# zesilovac.net
KiCad netlist of a schematic drawn in EAGLE
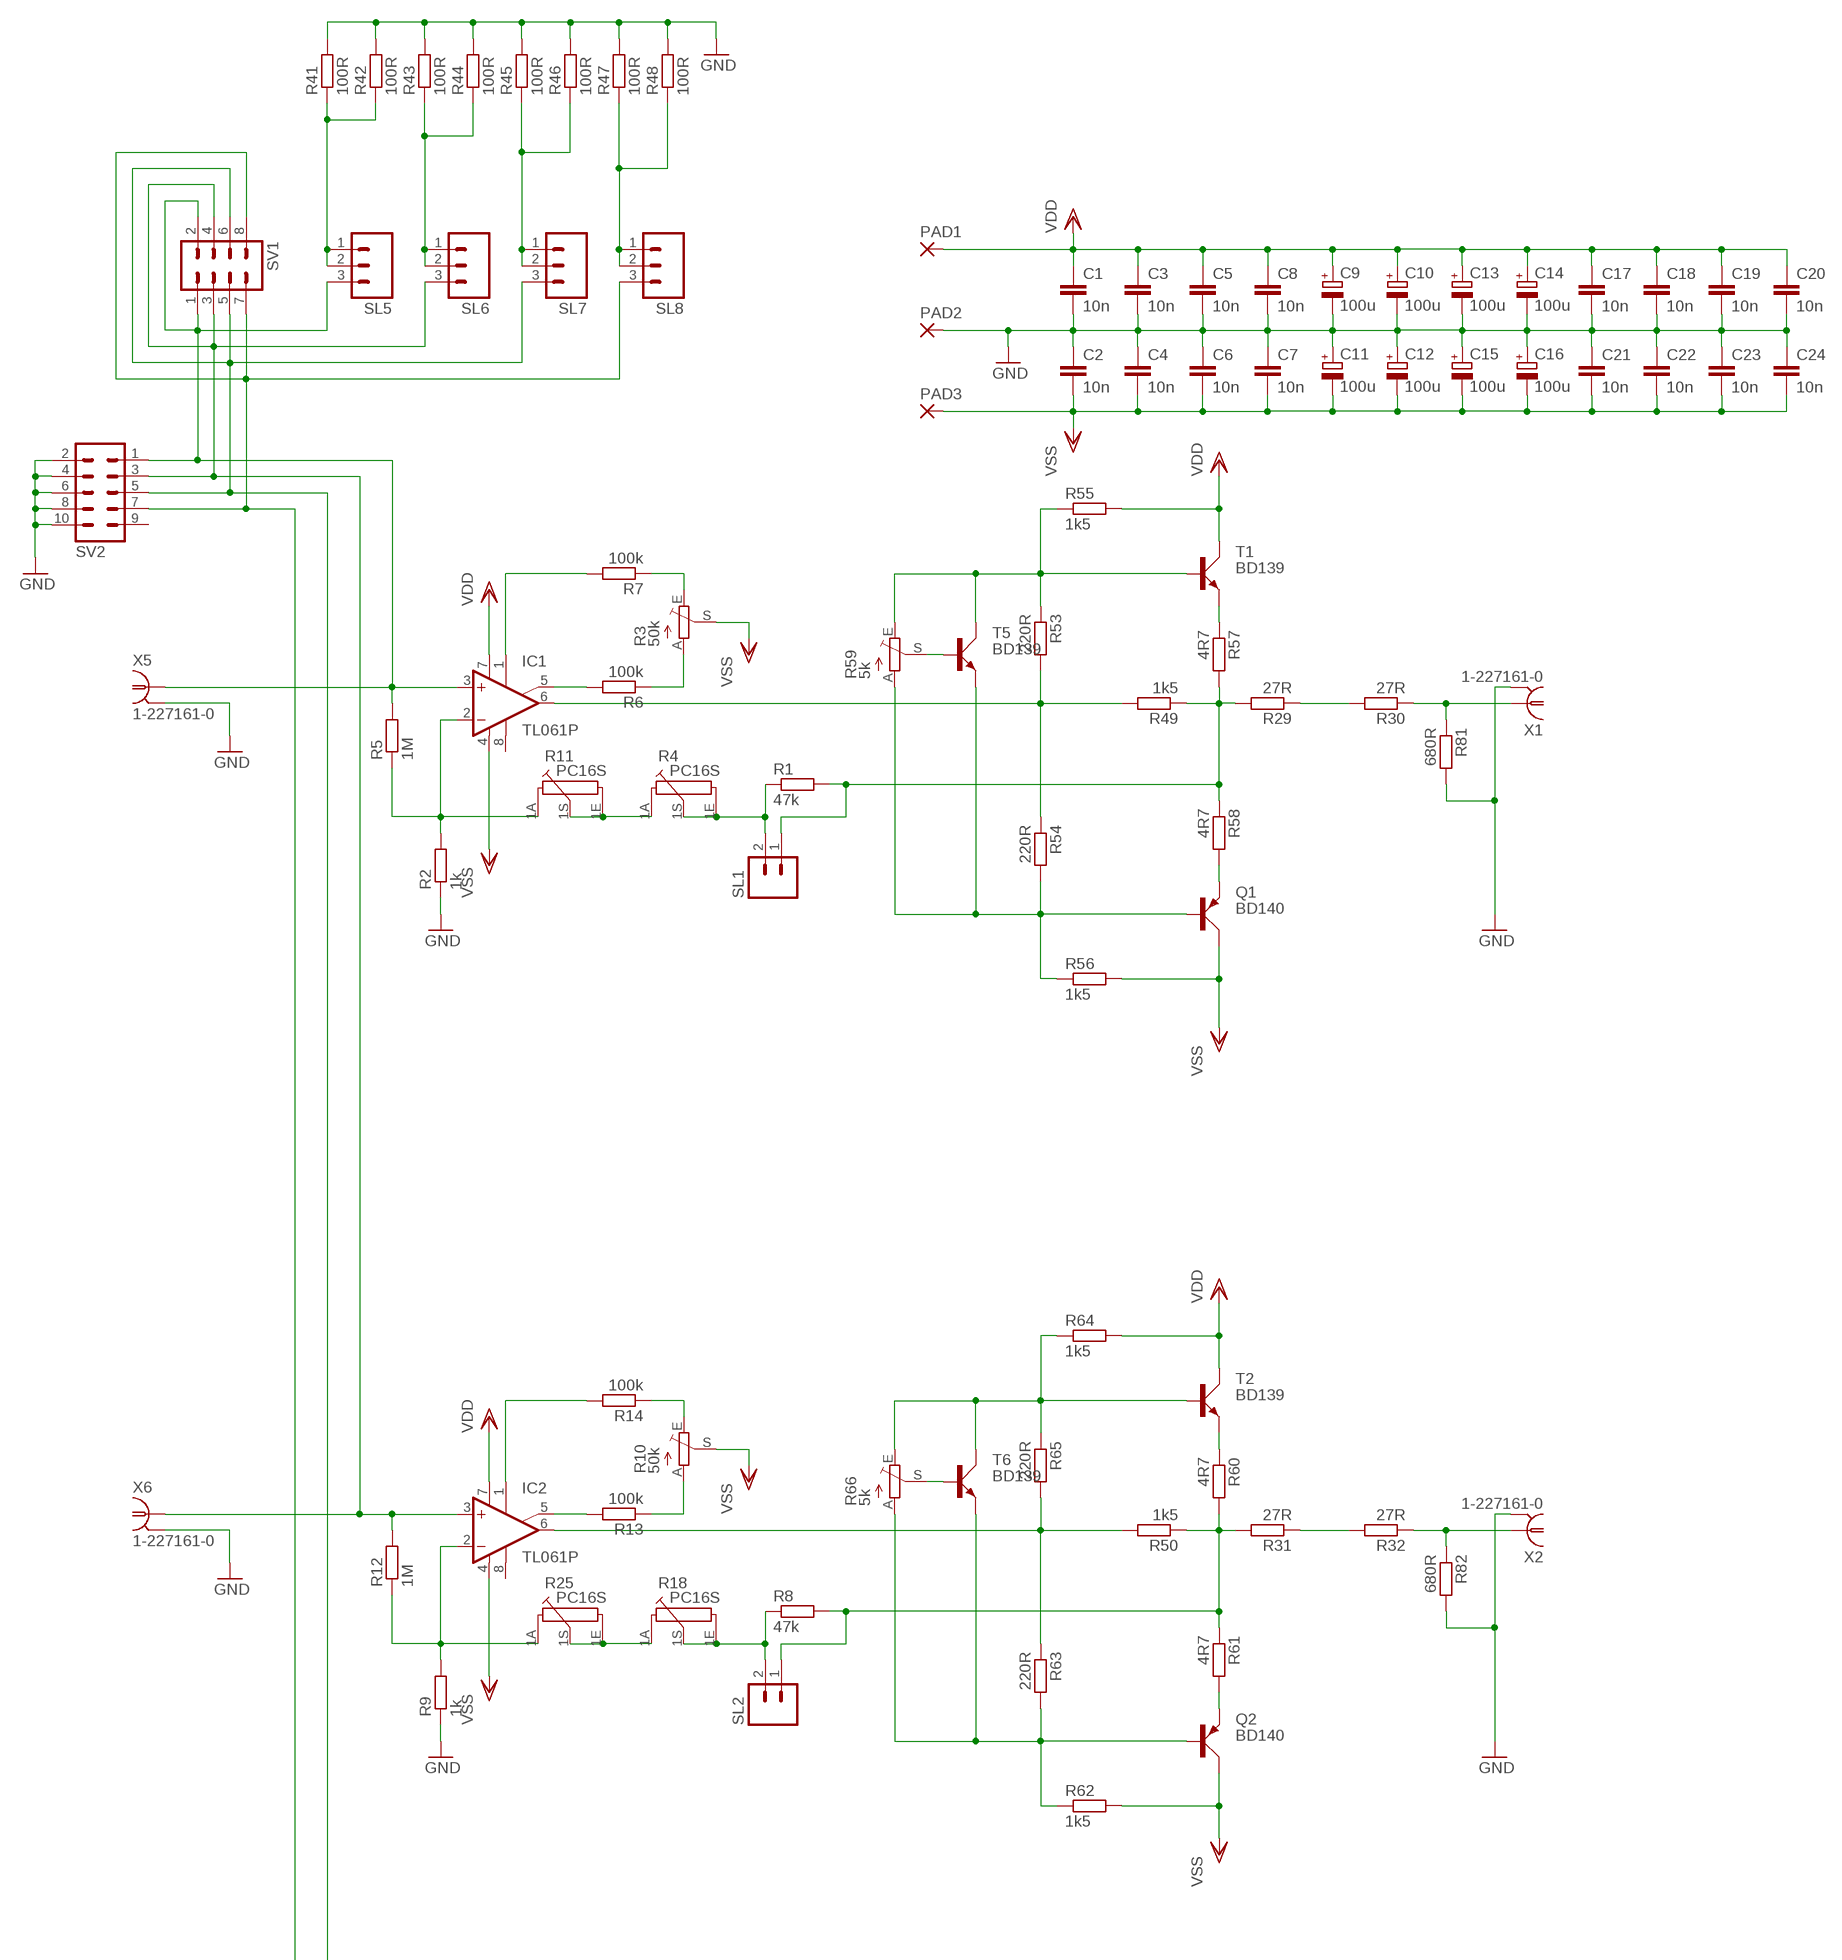
[diagram p0: schematic, sheet 1, part 1 of 2]
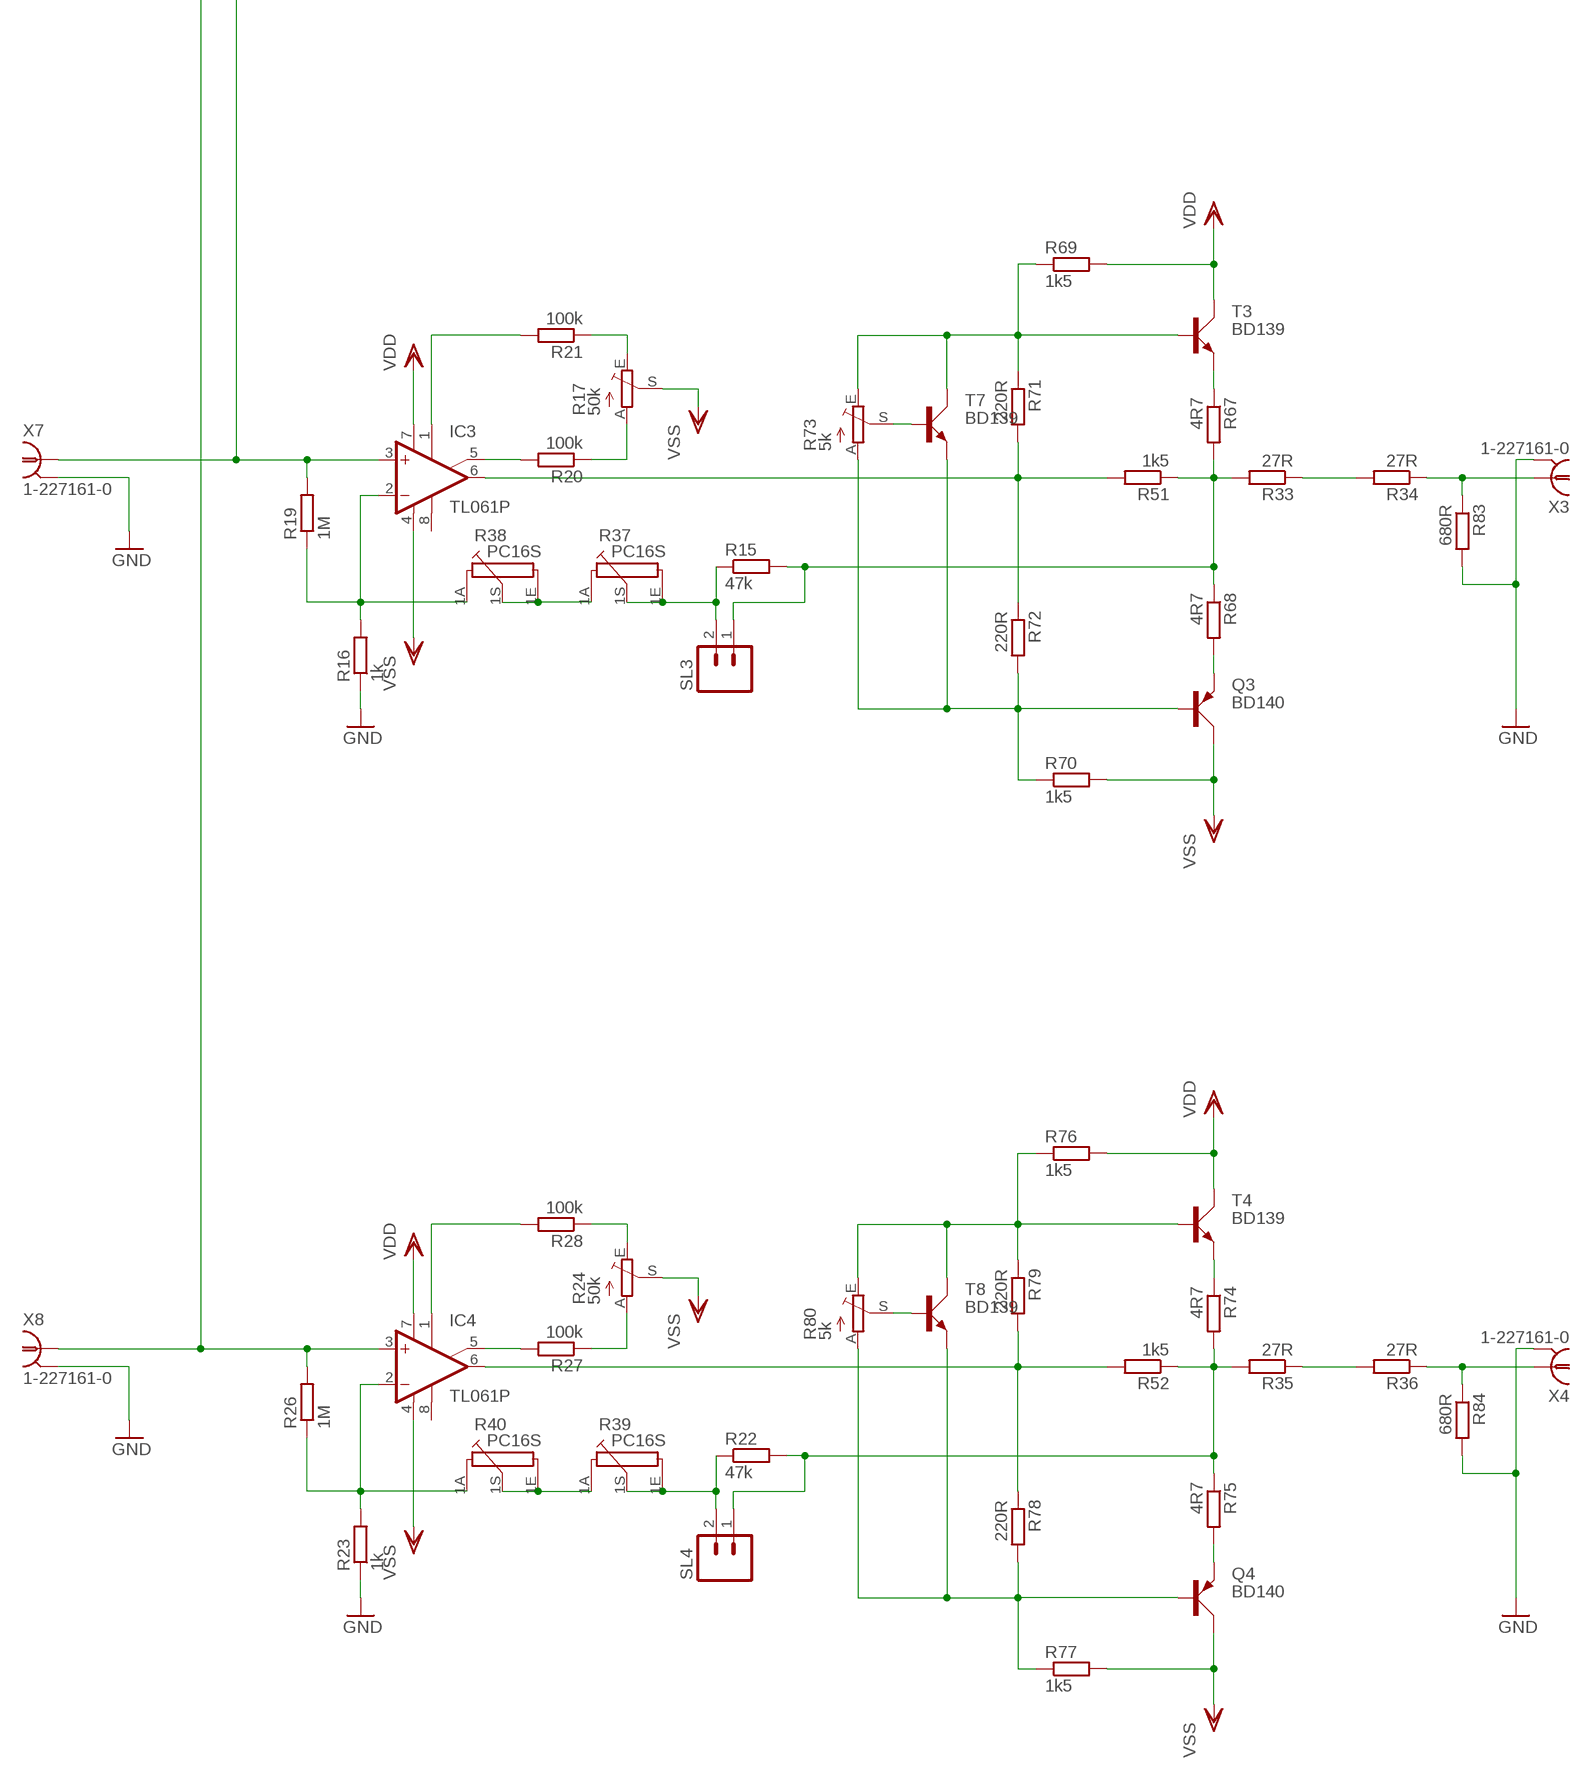
[diagram p1: schematic, sheet 1, part 2 of 2]

(export (version "E")
  (design (tool "Eeschema 10.0.6"))
  (components
    (comp (ref "C1")
      (value "10n")
      (footprint "eagle-import:C5B5")
      (libsource (lib "eagle-import") (part "C5/5"))
    )
    (comp (ref "C2")
      (value "10n")
      (footprint "eagle-import:C5B5")
      (libsource (lib "eagle-import") (part "C5/5"))
    )
    (comp (ref "C3")
      (value "10n")
      (footprint "eagle-import:C5B5")
      (libsource (lib "eagle-import") (part "C5/5"))
    )
    (comp (ref "C4")
      (value "10n")
      (footprint "eagle-import:C5B5")
      (libsource (lib "eagle-import") (part "C5/5"))
    )
    (comp (ref "C5")
      (value "10n")
      (footprint "eagle-import:C5B5")
      (libsource (lib "eagle-import") (part "C5/5"))
    )
    (comp (ref "C6")
      (value "10n")
      (footprint "eagle-import:C5B5")
      (libsource (lib "eagle-import") (part "C5/5"))
    )
    (comp (ref "C7")
      (value "10n")
      (footprint "eagle-import:C5B5")
      (libsource (lib "eagle-import") (part "C5/5"))
    )
    (comp (ref "C8")
      (value "10n")
      (footprint "eagle-import:C5B5")
      (libsource (lib "eagle-import") (part "C5/5"))
    )
    (comp (ref "C9")
      (value "100u")
      (footprint "eagle-import:E5-13")
      (libsource (lib "eagle-import") (part "CPOL-EUE5-13"))
    )
    (comp (ref "C10")
      (value "100u")
      (footprint "eagle-import:E5-13")
      (libsource (lib "eagle-import") (part "CPOL-EUE5-13"))
    )
    (comp (ref "C11")
      (value "100u")
      (footprint "eagle-import:E5-13")
      (libsource (lib "eagle-import") (part "CPOL-EUE5-13"))
    )
    (comp (ref "C12")
      (value "100u")
      (footprint "eagle-import:E5-13")
      (libsource (lib "eagle-import") (part "CPOL-EUE5-13"))
    )
    (comp (ref "C13")
      (value "100u")
      (footprint "eagle-import:E5-13")
      (libsource (lib "eagle-import") (part "CPOL-EUE5-13"))
    )
    (comp (ref "C14")
      (value "100u")
      (footprint "eagle-import:E5-13")
      (libsource (lib "eagle-import") (part "CPOL-EUE5-13"))
    )
    (comp (ref "C15")
      (value "100u")
      (footprint "eagle-import:E5-13")
      (libsource (lib "eagle-import") (part "CPOL-EUE5-13"))
    )
    (comp (ref "C16")
      (value "100u")
      (footprint "eagle-import:E5-13")
      (libsource (lib "eagle-import") (part "CPOL-EUE5-13"))
    )
    (comp (ref "C17")
      (value "10n")
      (footprint "eagle-import:C5B5")
      (libsource (lib "eagle-import") (part "C5/5"))
    )
    (comp (ref "C18")
      (value "10n")
      (footprint "eagle-import:C5B5")
      (libsource (lib "eagle-import") (part "C5/5"))
    )
    (comp (ref "C19")
      (value "10n")
      (footprint "eagle-import:C5B5")
      (libsource (lib "eagle-import") (part "C5/5"))
    )
    (comp (ref "C20")
      (value "10n")
      (footprint "eagle-import:C5B5")
      (libsource (lib "eagle-import") (part "C5/5"))
    )
    (comp (ref "C21")
      (value "10n")
      (footprint "eagle-import:C5B5")
      (libsource (lib "eagle-import") (part "C5/5"))
    )
    (comp (ref "C22")
      (value "10n")
      (footprint "eagle-import:C5B5")
      (libsource (lib "eagle-import") (part "C5/5"))
    )
    (comp (ref "C23")
      (value "10n")
      (footprint "eagle-import:C5B5")
      (libsource (lib "eagle-import") (part "C5/5"))
    )
    (comp (ref "C24")
      (value "10n")
      (footprint "eagle-import:C5B5")
      (libsource (lib "eagle-import") (part "C5/5"))
    )
    (comp (ref "IC1")
      (value "TL061P")
      (footprint "eagle-import:DIL08")
      (libsource (lib "eagle-import") (part "TL061P"))
    )
    (comp (ref "IC2")
      (value "TL061P")
      (footprint "eagle-import:DIL08")
      (libsource (lib "eagle-import") (part "TL061P"))
    )
    (comp (ref "IC3")
      (value "TL061P")
      (footprint "eagle-import:DIL08")
      (libsource (lib "eagle-import") (part "TL061P"))
    )
    (comp (ref "IC4")
      (value "TL061P")
      (footprint "eagle-import:DIL08")
      (libsource (lib "eagle-import") (part "TL061P"))
    )
    (comp (ref "PAD1")
      (value "3,81/1,4")
      (footprint "eagle-import:3,81_1,4")
      (libsource (lib "eagle-import") (part "3,81/1,4"))
    )
    (comp (ref "PAD2")
      (value "3,81/1,4")
      (footprint "eagle-import:3,81_1,4")
      (libsource (lib "eagle-import") (part "3,81/1,4"))
    )
    (comp (ref "PAD3")
      (value "3,81/1,4")
      (footprint "eagle-import:3,81_1,4")
      (libsource (lib "eagle-import") (part "3,81/1,4"))
    )
    (comp (ref "Q1")
      (value "BD140")
      (footprint "eagle-import:TO126AV")
      (libsource (lib "eagle-import") (part "BD140"))
    )
    (comp (ref "Q2")
      (value "BD140")
      (footprint "eagle-import:TO126AV")
      (libsource (lib "eagle-import") (part "BD140"))
    )
    (comp (ref "Q3")
      (value "BD140")
      (footprint "eagle-import:TO126AV")
      (libsource (lib "eagle-import") (part "BD140"))
    )
    (comp (ref "Q4")
      (value "BD140")
      (footprint "eagle-import:TO126AV")
      (libsource (lib "eagle-import") (part "BD140"))
    )
    (comp (ref "R1")
      (value "47k")
      (footprint "eagle-import:0207_12")
      (libsource (lib "eagle-import") (part "R-EU_0207/12"))
    )
    (comp (ref "R2")
      (value "1k")
      (footprint "eagle-import:0207_12")
      (libsource (lib "eagle-import") (part "R-EU_0207/12"))
    )
    (comp (ref "R3")
      (value "50k")
      (footprint "eagle-import:LI10")
      (libsource (lib "eagle-import") (part "TRIM_EU-LI10"))
    )
    (comp (ref "R4")
      (value "PC16S")
      (footprint "eagle-import:PC16S")
      (libsource (lib "eagle-import") (part "PC16S"))
    )
    (comp (ref "R5")
      (value "1M")
      (footprint "eagle-import:0207_12")
      (libsource (lib "eagle-import") (part "R-EU_0207/12"))
    )
    (comp (ref "R6")
      (value "100k")
      (footprint "eagle-import:0207_12")
      (libsource (lib "eagle-import") (part "R-EU_0207/12"))
    )
    (comp (ref "R7")
      (value "100k")
      (footprint "eagle-import:0207_12")
      (libsource (lib "eagle-import") (part "R-EU_0207/12"))
    )
    (comp (ref "R8")
      (value "47k")
      (footprint "eagle-import:0207_12")
      (libsource (lib "eagle-import") (part "R-EU_0207/12"))
    )
    (comp (ref "R9")
      (value "1k")
      (footprint "eagle-import:0207_12")
      (libsource (lib "eagle-import") (part "R-EU_0207/12"))
    )
    (comp (ref "R10")
      (value "50k")
      (footprint "eagle-import:LI10")
      (libsource (lib "eagle-import") (part "TRIM_EU-LI10"))
    )
    (comp (ref "R11")
      (value "PC16S")
      (footprint "eagle-import:PC16S")
      (libsource (lib "eagle-import") (part "PC16S"))
    )
    (comp (ref "R12")
      (value "1M")
      (footprint "eagle-import:0207_12")
      (libsource (lib "eagle-import") (part "R-EU_0207/12"))
    )
    (comp (ref "R13")
      (value "100k")
      (footprint "eagle-import:0207_12")
      (libsource (lib "eagle-import") (part "R-EU_0207/12"))
    )
    (comp (ref "R14")
      (value "100k")
      (footprint "eagle-import:0207_12")
      (libsource (lib "eagle-import") (part "R-EU_0207/12"))
    )
    (comp (ref "R15")
      (value "47k")
      (footprint "eagle-import:0207_12")
      (libsource (lib "eagle-import") (part "R-EU_0207/12"))
    )
    (comp (ref "R16")
      (value "1k")
      (footprint "eagle-import:0207_12")
      (libsource (lib "eagle-import") (part "R-EU_0207/12"))
    )
    (comp (ref "R17")
      (value "50k")
      (footprint "eagle-import:LI10")
      (libsource (lib "eagle-import") (part "TRIM_EU-LI10"))
    )
    (comp (ref "R18")
      (value "PC16S")
      (footprint "eagle-import:PC16S")
      (libsource (lib "eagle-import") (part "PC16S"))
    )
    (comp (ref "R19")
      (value "1M")
      (footprint "eagle-import:0207_12")
      (libsource (lib "eagle-import") (part "R-EU_0207/12"))
    )
    (comp (ref "R20")
      (value "100k")
      (footprint "eagle-import:0207_12")
      (libsource (lib "eagle-import") (part "R-EU_0207/12"))
    )
    (comp (ref "R21")
      (value "100k")
      (footprint "eagle-import:0207_12")
      (libsource (lib "eagle-import") (part "R-EU_0207/12"))
    )
    (comp (ref "R22")
      (value "47k")
      (footprint "eagle-import:0207_12")
      (libsource (lib "eagle-import") (part "R-EU_0207/12"))
    )
    (comp (ref "R23")
      (value "1k")
      (footprint "eagle-import:0207_12")
      (libsource (lib "eagle-import") (part "R-EU_0207/12"))
    )
    (comp (ref "R24")
      (value "50k")
      (footprint "eagle-import:LI10")
      (libsource (lib "eagle-import") (part "TRIM_EU-LI10"))
    )
    (comp (ref "R25")
      (value "PC16S")
      (footprint "eagle-import:PC16S")
      (libsource (lib "eagle-import") (part "PC16S"))
    )
    (comp (ref "R26")
      (value "1M")
      (footprint "eagle-import:0207_12")
      (libsource (lib "eagle-import") (part "R-EU_0207/12"))
    )
    (comp (ref "R27")
      (value "100k")
      (footprint "eagle-import:0207_12")
      (libsource (lib "eagle-import") (part "R-EU_0207/12"))
    )
    (comp (ref "R28")
      (value "100k")
      (footprint "eagle-import:0207_12")
      (libsource (lib "eagle-import") (part "R-EU_0207/12"))
    )
    (comp (ref "R29")
      (value "27R")
      (footprint "eagle-import:0411_12")
      (libsource (lib "eagle-import") (part "R-EU_0411/12"))
    )
    (comp (ref "R30")
      (value "27R")
      (footprint "eagle-import:0411_12")
      (libsource (lib "eagle-import") (part "R-EU_0411/12"))
    )
    (comp (ref "R31")
      (value "27R")
      (footprint "eagle-import:0411_12")
      (libsource (lib "eagle-import") (part "R-EU_0411/12"))
    )
    (comp (ref "R32")
      (value "27R")
      (footprint "eagle-import:0411_12")
      (libsource (lib "eagle-import") (part "R-EU_0411/12"))
    )
    (comp (ref "R33")
      (value "27R")
      (footprint "eagle-import:0411_12")
      (libsource (lib "eagle-import") (part "R-EU_0411/12"))
    )
    (comp (ref "R34")
      (value "27R")
      (footprint "eagle-import:0411_12")
      (libsource (lib "eagle-import") (part "R-EU_0411/12"))
    )
    (comp (ref "R35")
      (value "27R")
      (footprint "eagle-import:0411_12")
      (libsource (lib "eagle-import") (part "R-EU_0411/12"))
    )
    (comp (ref "R36")
      (value "27R")
      (footprint "eagle-import:0411_12")
      (libsource (lib "eagle-import") (part "R-EU_0411/12"))
    )
    (comp (ref "R37")
      (value "PC16S")
      (footprint "eagle-import:PC16S")
      (libsource (lib "eagle-import") (part "PC16S"))
    )
    (comp (ref "R38")
      (value "PC16S")
      (footprint "eagle-import:PC16S")
      (libsource (lib "eagle-import") (part "PC16S"))
    )
    (comp (ref "R39")
      (value "PC16S")
      (footprint "eagle-import:PC16S")
      (libsource (lib "eagle-import") (part "PC16S"))
    )
    (comp (ref "R40")
      (value "PC16S")
      (footprint "eagle-import:PC16S")
      (libsource (lib "eagle-import") (part "PC16S"))
    )
    (comp (ref "R41")
      (value "100R")
      (footprint "eagle-import:0207_12")
      (libsource (lib "eagle-import") (part "R-EU_0207/12"))
    )
    (comp (ref "R42")
      (value "100R")
      (footprint "eagle-import:0207_12")
      (libsource (lib "eagle-import") (part "R-EU_0207/12"))
    )
    (comp (ref "R43")
      (value "100R")
      (footprint "eagle-import:0207_12")
      (libsource (lib "eagle-import") (part "R-EU_0207/12"))
    )
    (comp (ref "R44")
      (value "100R")
      (footprint "eagle-import:0207_12")
      (libsource (lib "eagle-import") (part "R-EU_0207/12"))
    )
    (comp (ref "R45")
      (value "100R")
      (footprint "eagle-import:0207_12")
      (libsource (lib "eagle-import") (part "R-EU_0207/12"))
    )
    (comp (ref "R46")
      (value "100R")
      (footprint "eagle-import:0207_12")
      (libsource (lib "eagle-import") (part "R-EU_0207/12"))
    )
    (comp (ref "R47")
      (value "100R")
      (footprint "eagle-import:0207_12")
      (libsource (lib "eagle-import") (part "R-EU_0207/12"))
    )
    (comp (ref "R48")
      (value "100R")
      (footprint "eagle-import:0207_12")
      (libsource (lib "eagle-import") (part "R-EU_0207/12"))
    )
    (comp (ref "R49")
      (value "1k5")
      (footprint "eagle-import:0207_12")
      (libsource (lib "eagle-import") (part "R-EU_0207/12"))
    )
    (comp (ref "R50")
      (value "1k5")
      (footprint "eagle-import:0207_12")
      (libsource (lib "eagle-import") (part "R-EU_0207/12"))
    )
    (comp (ref "R51")
      (value "1k5")
      (footprint "eagle-import:0207_12")
      (libsource (lib "eagle-import") (part "R-EU_0207/12"))
    )
    (comp (ref "R52")
      (value "1k5")
      (footprint "eagle-import:0207_12")
      (libsource (lib "eagle-import") (part "R-EU_0207/12"))
    )
    (comp (ref "R53")
      (value "220R")
      (footprint "eagle-import:0207_12")
      (libsource (lib "eagle-import") (part "R-EU_0207/12"))
    )
    (comp (ref "R54")
      (value "220R")
      (footprint "eagle-import:0207_12")
      (libsource (lib "eagle-import") (part "R-EU_0207/12"))
    )
    (comp (ref "R55")
      (value "1k5")
      (footprint "eagle-import:0207_12")
      (libsource (lib "eagle-import") (part "R-EU_0207/12"))
    )
    (comp (ref "R56")
      (value "1k5")
      (footprint "eagle-import:0207_12")
      (libsource (lib "eagle-import") (part "R-EU_0207/12"))
    )
    (comp (ref "R57")
      (value "4R7")
      (footprint "eagle-import:0207_12")
      (libsource (lib "eagle-import") (part "R-EU_0207/12"))
    )
    (comp (ref "R58")
      (value "4R7")
      (footprint "eagle-import:0207_12")
      (libsource (lib "eagle-import") (part "R-EU_0207/12"))
    )
    (comp (ref "R59")
      (value "5k")
      (footprint "eagle-import:LI10")
      (libsource (lib "eagle-import") (part "TRIM_EU-LI10"))
    )
    (comp (ref "R60")
      (value "4R7")
      (footprint "eagle-import:0207_12")
      (libsource (lib "eagle-import") (part "R-EU_0207/12"))
    )
    (comp (ref "R61")
      (value "4R7")
      (footprint "eagle-import:0207_12")
      (libsource (lib "eagle-import") (part "R-EU_0207/12"))
    )
    (comp (ref "R62")
      (value "1k5")
      (footprint "eagle-import:0207_12")
      (libsource (lib "eagle-import") (part "R-EU_0207/12"))
    )
    (comp (ref "R63")
      (value "220R")
      (footprint "eagle-import:0207_12")
      (libsource (lib "eagle-import") (part "R-EU_0207/12"))
    )
    (comp (ref "R64")
      (value "1k5")
      (footprint "eagle-import:0207_12")
      (libsource (lib "eagle-import") (part "R-EU_0207/12"))
    )
    (comp (ref "R65")
      (value "220R")
      (footprint "eagle-import:0207_12")
      (libsource (lib "eagle-import") (part "R-EU_0207/12"))
    )
    (comp (ref "R66")
      (value "5k")
      (footprint "eagle-import:LI10")
      (libsource (lib "eagle-import") (part "TRIM_EU-LI10"))
    )
    (comp (ref "R67")
      (value "4R7")
      (footprint "eagle-import:0207_12")
      (libsource (lib "eagle-import") (part "R-EU_0207/12"))
    )
    (comp (ref "R68")
      (value "4R7")
      (footprint "eagle-import:0207_12")
      (libsource (lib "eagle-import") (part "R-EU_0207/12"))
    )
    (comp (ref "R69")
      (value "1k5")
      (footprint "eagle-import:0207_12")
      (libsource (lib "eagle-import") (part "R-EU_0207/12"))
    )
    (comp (ref "R70")
      (value "1k5")
      (footprint "eagle-import:0207_12")
      (libsource (lib "eagle-import") (part "R-EU_0207/12"))
    )
    (comp (ref "R71")
      (value "220R")
      (footprint "eagle-import:0207_12")
      (libsource (lib "eagle-import") (part "R-EU_0207/12"))
    )
    (comp (ref "R72")
      (value "220R")
      (footprint "eagle-import:0207_12")
      (libsource (lib "eagle-import") (part "R-EU_0207/12"))
    )
    (comp (ref "R73")
      (value "5k")
      (footprint "eagle-import:LI10")
      (libsource (lib "eagle-import") (part "TRIM_EU-LI10"))
    )
    (comp (ref "R74")
      (value "4R7")
      (footprint "eagle-import:0207_12")
      (libsource (lib "eagle-import") (part "R-EU_0207/12"))
    )
    (comp (ref "R75")
      (value "4R7")
      (footprint "eagle-import:0207_12")
      (libsource (lib "eagle-import") (part "R-EU_0207/12"))
    )
    (comp (ref "R76")
      (value "1k5")
      (footprint "eagle-import:0207_12")
      (libsource (lib "eagle-import") (part "R-EU_0207/12"))
    )
    (comp (ref "R77")
      (value "1k5")
      (footprint "eagle-import:0207_12")
      (libsource (lib "eagle-import") (part "R-EU_0207/12"))
    )
    (comp (ref "R78")
      (value "220R")
      (footprint "eagle-import:0207_12")
      (libsource (lib "eagle-import") (part "R-EU_0207/12"))
    )
    (comp (ref "R79")
      (value "220R")
      (footprint "eagle-import:0207_12")
      (libsource (lib "eagle-import") (part "R-EU_0207/12"))
    )
    (comp (ref "R80")
      (value "5k")
      (footprint "eagle-import:LI10")
      (libsource (lib "eagle-import") (part "TRIM_EU-LI10"))
    )
    (comp (ref "R81")
      (value "680R")
      (footprint "eagle-import:0207_12")
      (libsource (lib "eagle-import") (part "R-EU_0207/12"))
    )
    (comp (ref "R82")
      (value "680R")
      (footprint "eagle-import:0207_12")
      (libsource (lib "eagle-import") (part "R-EU_0207/12"))
    )
    (comp (ref "R83")
      (value "680R")
      (footprint "eagle-import:0207_12")
      (libsource (lib "eagle-import") (part "R-EU_0207/12"))
    )
    (comp (ref "R84")
      (value "680R")
      (footprint "eagle-import:0207_12")
      (libsource (lib "eagle-import") (part "R-EU_0207/12"))
    )
    (comp (ref "SL1")
      (value "M02")
      (footprint "eagle-import:02P")
      (libsource (lib "eagle-import") (part "M02"))
    )
    (comp (ref "SL2")
      (value "M02")
      (footprint "eagle-import:02P")
      (libsource (lib "eagle-import") (part "M02"))
    )
    (comp (ref "SL3")
      (value "M02")
      (footprint "eagle-import:02P")
      (libsource (lib "eagle-import") (part "M02"))
    )
    (comp (ref "SL4")
      (value "M02")
      (footprint "eagle-import:02P")
      (libsource (lib "eagle-import") (part "M02"))
    )
    (comp (ref "SL5")
      (value "M03")
      (footprint "eagle-import:03P")
      (libsource (lib "eagle-import") (part "M03"))
    )
    (comp (ref "SL6")
      (value "M03")
      (footprint "eagle-import:03P")
      (libsource (lib "eagle-import") (part "M03"))
    )
    (comp (ref "SL7")
      (value "M03")
      (footprint "eagle-import:03P")
      (libsource (lib "eagle-import") (part "M03"))
    )
    (comp (ref "SL8")
      (value "M03")
      (footprint "eagle-import:03P")
      (libsource (lib "eagle-import") (part "M03"))
    )
    (comp (ref "SV1")
      (value "MA04-2")
      (footprint "eagle-import:MA04-2")
      (libsource (lib "eagle-import") (part "MA04-2"))
    )
    (comp (ref "SV2")
      (value "MA05-2")
      (footprint "eagle-import:MA05-2")
      (libsource (lib "eagle-import") (part "MA05-2"))
    )
    (comp (ref "T1")
      (value "BD139")
      (footprint "eagle-import:TO126AV")
      (libsource (lib "eagle-import") (part "BD139"))
    )
    (comp (ref "T2")
      (value "BD139")
      (footprint "eagle-import:TO126AV")
      (libsource (lib "eagle-import") (part "BD139"))
    )
    (comp (ref "T3")
      (value "BD139")
      (footprint "eagle-import:TO126AV")
      (libsource (lib "eagle-import") (part "BD139"))
    )
    (comp (ref "T4")
      (value "BD139")
      (footprint "eagle-import:TO126AV")
      (libsource (lib "eagle-import") (part "BD139"))
    )
    (comp (ref "T5")
      (value "BD139")
      (footprint "eagle-import:TO126AV")
      (libsource (lib "eagle-import") (part "BD139"))
    )
    (comp (ref "T6")
      (value "BD139")
      (footprint "eagle-import:TO126AV")
      (libsource (lib "eagle-import") (part "BD139"))
    )
    (comp (ref "T7")
      (value "BD139")
      (footprint "eagle-import:TO126AV")
      (libsource (lib "eagle-import") (part "BD139"))
    )
    (comp (ref "T8")
      (value "BD139")
      (footprint "eagle-import:TO126AV")
      (libsource (lib "eagle-import") (part "BD139"))
    )
    (comp (ref "X1")
      (value "1-227161-0")
      (footprint "eagle-import:AMP_227161")
      (fields (field (name "MF") "TYCO ELECTRONICS") (field (name "MPN") "1-227161"))
      (libsource (lib "eagle-import") (part "?2271611--0"))
    )
    (comp (ref "X2")
      (value "1-227161-0")
      (footprint "eagle-import:AMP_227161")
      (fields (field (name "MF") "TYCO ELECTRONICS") (field (name "MPN") "1-227161"))
      (libsource (lib "eagle-import") (part "?2271611--0"))
    )
    (comp (ref "X3")
      (value "1-227161-0")
      (footprint "eagle-import:AMP_227161")
      (fields (field (name "MF") "TYCO ELECTRONICS") (field (name "MPN") "1-227161"))
      (libsource (lib "eagle-import") (part "?2271611--0"))
    )
    (comp (ref "X4")
      (value "1-227161-0")
      (footprint "eagle-import:AMP_227161")
      (fields (field (name "MF") "TYCO ELECTRONICS") (field (name "MPN") "1-227161"))
      (libsource (lib "eagle-import") (part "?2271611--0"))
    )
    (comp (ref "X5")
      (value "1-227161-0")
      (footprint "eagle-import:AMP_227161")
      (fields (field (name "MF") "TYCO ELECTRONICS") (field (name "MPN") "1-227161"))
      (libsource (lib "eagle-import") (part "?2271611--0"))
    )
    (comp (ref "X6")
      (value "1-227161-0")
      (footprint "eagle-import:AMP_227161")
      (fields (field (name "MF") "TYCO ELECTRONICS") (field (name "MPN") "1-227161"))
      (libsource (lib "eagle-import") (part "?2271611--0"))
    )
    (comp (ref "X7")
      (value "1-227161-0")
      (footprint "eagle-import:AMP_227161")
      (fields (field (name "MF") "TYCO ELECTRONICS") (field (name "MPN") "1-227161"))
      (libsource (lib "eagle-import") (part "?2271611--0"))
    )
    (comp (ref "X8")
      (value "1-227161-0")
      (footprint "eagle-import:AMP_227161")
      (fields (field (name "MF") "TYCO ELECTRONICS") (field (name "MPN") "1-227161"))
      (libsource (lib "eagle-import") (part "?2271611--0"))
    )
  )
  (nets
    (net (code "1") (name "GND") (class "Default")
      (node (ref "C1") (pin "2") (pinfunction "2_2") (pintype "passive"))
      (node (ref "C10") (pin "-") (pinfunction "-_-") (pintype "passive"))
      (node (ref "C11") (pin "+") (pinfunction "+_+") (pintype "passive"))
      (node (ref "C12") (pin "+") (pinfunction "+_+") (pintype "passive"))
      (node (ref "C13") (pin "-") (pinfunction "-_-") (pintype "passive"))
      (node (ref "C14") (pin "-") (pinfunction "-_-") (pintype "passive"))
      (node (ref "C15") (pin "+") (pinfunction "+_+") (pintype "passive"))
      (node (ref "C16") (pin "+") (pinfunction "+_+") (pintype "passive"))
      (node (ref "C17") (pin "2") (pinfunction "2_2") (pintype "passive"))
      (node (ref "C18") (pin "2") (pinfunction "2_2") (pintype "passive"))
      (node (ref "C19") (pin "2") (pinfunction "2_2") (pintype "passive"))
      (node (ref "C2") (pin "1") (pinfunction "1_1") (pintype "passive"))
      (node (ref "C20") (pin "2") (pinfunction "2_2") (pintype "passive"))
      (node (ref "C21") (pin "1") (pinfunction "1_1") (pintype "passive"))
      (node (ref "C22") (pin "1") (pinfunction "1_1") (pintype "passive"))
      (node (ref "C23") (pin "1") (pinfunction "1_1") (pintype "passive"))
      (node (ref "C24") (pin "1") (pinfunction "1_1") (pintype "passive"))
      (node (ref "C3") (pin "2") (pinfunction "2_2") (pintype "passive"))
      (node (ref "C4") (pin "1") (pinfunction "1_1") (pintype "passive"))
      (node (ref "C5") (pin "2") (pinfunction "2_2") (pintype "passive"))
      (node (ref "C6") (pin "1") (pinfunction "1_1") (pintype "passive"))
      (node (ref "C7") (pin "1") (pinfunction "1_1") (pintype "passive"))
      (node (ref "C8") (pin "2") (pinfunction "2_2") (pintype "passive"))
      (node (ref "C9") (pin "-") (pinfunction "-_-") (pintype "passive"))
      (node (ref "PAD2") (pin "1") (pinfunction "P_1") (pintype "passive"))
      (node (ref "R16") (pin "1") (pinfunction "1_1") (pintype "passive"))
      (node (ref "R2") (pin "1") (pinfunction "1_1") (pintype "passive"))
      (node (ref "R23") (pin "1") (pinfunction "1_1") (pintype "passive"))
      (node (ref "R41") (pin "2") (pinfunction "2_2") (pintype "passive"))
      (node (ref "R42") (pin "2") (pinfunction "2_2") (pintype "passive"))
      (node (ref "R43") (pin "2") (pinfunction "2_2") (pintype "passive"))
      (node (ref "R44") (pin "2") (pinfunction "2_2") (pintype "passive"))
      (node (ref "R45") (pin "2") (pinfunction "2_2") (pintype "passive"))
      (node (ref "R46") (pin "2") (pinfunction "2_2") (pintype "passive"))
      (node (ref "R47") (pin "2") (pinfunction "2_2") (pintype "passive"))
      (node (ref "R48") (pin "2") (pinfunction "2_2") (pintype "passive"))
      (node (ref "R81") (pin "2") (pinfunction "2_2") (pintype "passive"))
      (node (ref "R82") (pin "2") (pinfunction "2_2") (pintype "passive"))
      (node (ref "R83") (pin "2") (pinfunction "2_2") (pintype "passive"))
      (node (ref "R84") (pin "2") (pinfunction "2_2") (pintype "passive"))
      (node (ref "R9") (pin "1") (pinfunction "1_1") (pintype "passive"))
      (node (ref "SV2") (pin "10") (pinfunction "10_10") (pintype "passive"))
      (node (ref "SV2") (pin "2") (pinfunction "2_2") (pintype "passive"))
      (node (ref "SV2") (pin "4") (pinfunction "4_4") (pintype "passive"))
      (node (ref "SV2") (pin "6") (pinfunction "6_6") (pintype "passive"))
      (node (ref "SV2") (pin "8") (pinfunction "8_8") (pintype "passive"))
      (node (ref "X1") (pin "2") (pinfunction "2_2") (pintype "passive"))
      (node (ref "X2") (pin "2") (pinfunction "2_2") (pintype "passive"))
      (node (ref "X3") (pin "2") (pinfunction "2_2") (pintype "passive"))
      (node (ref "X4") (pin "2") (pinfunction "2_2") (pintype "passive"))
      (node (ref "X5") (pin "2") (pinfunction "2_2") (pintype "passive"))
      (node (ref "X6") (pin "2") (pinfunction "2_2") (pintype "passive"))
      (node (ref "X7") (pin "2") (pinfunction "2_2") (pintype "passive"))
      (node (ref "X8") (pin "2") (pinfunction "2_2") (pintype "passive"))
    )
    (net (code "2") (name "Net-(IC1-+IN)") (class "Default")
      (node (ref "IC1") (pin "3") (pinfunction "+IN_3") (pintype "input"))
      (node (ref "R5") (pin "2") (pinfunction "2_2") (pintype "passive"))
      (node (ref "SL5") (pin "3") (pinfunction "3_3") (pintype "passive"))
      (node (ref "SV1") (pin "1") (pinfunction "1_1") (pintype "passive"))
      (node (ref "SV1") (pin "2") (pinfunction "2_2") (pintype "passive"))
      (node (ref "SV2") (pin "1") (pinfunction "1_1") (pintype "passive"))
      (node (ref "X5") (pin "1") (pinfunction "1_1") (pintype "passive"))
    )
    (net (code "3") (name "Net-(IC1--IN)") (class "Default")
      (node (ref "IC1") (pin "2") (pinfunction "-IN_2") (pintype "input"))
      (node (ref "R11") (pin "1A") (pinfunction "1A_1A") (pintype "passive"))
      (node (ref "R2") (pin "2") (pinfunction "2_2") (pintype "passive"))
      (node (ref "R5") (pin "1") (pinfunction "1_1") (pintype "passive"))
    )
    (net (code "4") (name "Net-(IC1-ON1)") (class "Default")
      (node (ref "IC1") (pin "1") (pinfunction "ON1_1") (pintype "passive"))
      (node (ref "R7") (pin "2") (pinfunction "2_2") (pintype "passive"))
    )
    (net (code "5") (name "Net-(IC1-ON2)") (class "Default")
      (node (ref "IC1") (pin "5") (pinfunction "ON2_5") (pintype "passive"))
      (node (ref "R6") (pin "2") (pinfunction "2_2") (pintype "passive"))
    )
    (net (code "6") (name "Net-(IC1-OUT)") (class "Default")
      (node (ref "IC1") (pin "6") (pinfunction "OUT_6") (pintype "output"))
      (node (ref "R49") (pin "2") (pinfunction "2_2") (pintype "passive"))
      (node (ref "R53") (pin "2") (pinfunction "2_2") (pintype "passive"))
      (node (ref "R54") (pin "1") (pinfunction "1_1") (pintype "passive"))
    )
    (net (code "7") (name "Net-(IC2-+IN)") (class "Default")
      (node (ref "IC2") (pin "3") (pinfunction "+IN_3") (pintype "input"))
      (node (ref "R12") (pin "2") (pinfunction "2_2") (pintype "passive"))
      (node (ref "SL6") (pin "3") (pinfunction "3_3") (pintype "passive"))
      (node (ref "SV1") (pin "3") (pinfunction "3_3") (pintype "passive"))
      (node (ref "SV1") (pin "4") (pinfunction "4_4") (pintype "passive"))
      (node (ref "SV2") (pin "3") (pinfunction "3_3") (pintype "passive"))
      (node (ref "X6") (pin "1") (pinfunction "1_1") (pintype "passive"))
    )
    (net (code "8") (name "Net-(IC2--IN)") (class "Default")
      (node (ref "IC2") (pin "2") (pinfunction "-IN_2") (pintype "input"))
      (node (ref "R12") (pin "1") (pinfunction "1_1") (pintype "passive"))
      (node (ref "R25") (pin "1A") (pinfunction "1A_1A") (pintype "passive"))
      (node (ref "R9") (pin "2") (pinfunction "2_2") (pintype "passive"))
    )
    (net (code "9") (name "Net-(IC2-ON1)") (class "Default")
      (node (ref "IC2") (pin "1") (pinfunction "ON1_1") (pintype "passive"))
      (node (ref "R14") (pin "2") (pinfunction "2_2") (pintype "passive"))
    )
    (net (code "10") (name "Net-(IC2-ON2)") (class "Default")
      (node (ref "IC2") (pin "5") (pinfunction "ON2_5") (pintype "passive"))
      (node (ref "R13") (pin "2") (pinfunction "2_2") (pintype "passive"))
    )
    (net (code "11") (name "Net-(IC2-OUT)") (class "Default")
      (node (ref "IC2") (pin "6") (pinfunction "OUT_6") (pintype "output"))
      (node (ref "R50") (pin "2") (pinfunction "2_2") (pintype "passive"))
      (node (ref "R63") (pin "1") (pinfunction "1_1") (pintype "passive"))
      (node (ref "R65") (pin "2") (pinfunction "2_2") (pintype "passive"))
    )
    (net (code "12") (name "Net-(IC3-+IN)") (class "Default")
      (node (ref "IC3") (pin "3") (pinfunction "+IN_3") (pintype "input"))
      (node (ref "R19") (pin "2") (pinfunction "2_2") (pintype "passive"))
      (node (ref "SL7") (pin "3") (pinfunction "3_3") (pintype "passive"))
      (node (ref "SV1") (pin "5") (pinfunction "5_5") (pintype "passive"))
      (node (ref "SV1") (pin "6") (pinfunction "6_6") (pintype "passive"))
      (node (ref "SV2") (pin "5") (pinfunction "5_5") (pintype "passive"))
      (node (ref "X7") (pin "1") (pinfunction "1_1") (pintype "passive"))
    )
    (net (code "13") (name "Net-(IC3--IN)") (class "Default")
      (node (ref "IC3") (pin "2") (pinfunction "-IN_2") (pintype "input"))
      (node (ref "R16") (pin "2") (pinfunction "2_2") (pintype "passive"))
      (node (ref "R19") (pin "1") (pinfunction "1_1") (pintype "passive"))
      (node (ref "R38") (pin "1A") (pinfunction "1A_1A") (pintype "passive"))
    )
    (net (code "14") (name "Net-(IC3-ON1)") (class "Default")
      (node (ref "IC3") (pin "1") (pinfunction "ON1_1") (pintype "passive"))
      (node (ref "R21") (pin "2") (pinfunction "2_2") (pintype "passive"))
    )
    (net (code "15") (name "Net-(IC3-ON2)") (class "Default")
      (node (ref "IC3") (pin "5") (pinfunction "ON2_5") (pintype "passive"))
      (node (ref "R20") (pin "2") (pinfunction "2_2") (pintype "passive"))
    )
    (net (code "16") (name "Net-(IC3-OUT)") (class "Default")
      (node (ref "IC3") (pin "6") (pinfunction "OUT_6") (pintype "output"))
      (node (ref "R51") (pin "2") (pinfunction "2_2") (pintype "passive"))
      (node (ref "R71") (pin "2") (pinfunction "2_2") (pintype "passive"))
      (node (ref "R72") (pin "1") (pinfunction "1_1") (pintype "passive"))
    )
    (net (code "17") (name "Net-(IC4-+IN)") (class "Default")
      (node (ref "IC4") (pin "3") (pinfunction "+IN_3") (pintype "input"))
      (node (ref "R26") (pin "2") (pinfunction "2_2") (pintype "passive"))
      (node (ref "SL8") (pin "3") (pinfunction "3_3") (pintype "passive"))
      (node (ref "SV1") (pin "7") (pinfunction "7_7") (pintype "passive"))
      (node (ref "SV1") (pin "8") (pinfunction "8_8") (pintype "passive"))
      (node (ref "SV2") (pin "7") (pinfunction "7_7") (pintype "passive"))
      (node (ref "X8") (pin "1") (pinfunction "1_1") (pintype "passive"))
    )
    (net (code "18") (name "Net-(IC4--IN)") (class "Default")
      (node (ref "IC4") (pin "2") (pinfunction "-IN_2") (pintype "input"))
      (node (ref "R23") (pin "2") (pinfunction "2_2") (pintype "passive"))
      (node (ref "R26") (pin "1") (pinfunction "1_1") (pintype "passive"))
      (node (ref "R40") (pin "1A") (pinfunction "1A_1A") (pintype "passive"))
    )
    (net (code "19") (name "Net-(IC4-ON1)") (class "Default")
      (node (ref "IC4") (pin "1") (pinfunction "ON1_1") (pintype "passive"))
      (node (ref "R28") (pin "2") (pinfunction "2_2") (pintype "passive"))
    )
    (net (code "20") (name "Net-(IC4-ON2)") (class "Default")
      (node (ref "IC4") (pin "5") (pinfunction "ON2_5") (pintype "passive"))
      (node (ref "R27") (pin "2") (pinfunction "2_2") (pintype "passive"))
    )
    (net (code "21") (name "Net-(IC4-OUT)") (class "Default")
      (node (ref "IC4") (pin "6") (pinfunction "OUT_6") (pintype "output"))
      (node (ref "R52") (pin "2") (pinfunction "2_2") (pintype "passive"))
      (node (ref "R78") (pin "1") (pinfunction "1_1") (pintype "passive"))
      (node (ref "R79") (pin "2") (pinfunction "2_2") (pintype "passive"))
    )
    (net (code "22") (name "Net-(Q1-PadB)") (class "Default")
      (node (ref "Q1") (pin "B") (pinfunction "B_B") (pintype "passive"))
      (node (ref "R54") (pin "2") (pinfunction "2_2") (pintype "passive"))
      (node (ref "R56") (pin "1") (pinfunction "1_1") (pintype "passive"))
      (node (ref "R59") (pin "A") (pinfunction "A_A") (pintype "passive"))
      (node (ref "T5") (pin "E") (pinfunction "E_E") (pintype "passive"))
    )
    (net (code "23") (name "Net-(Q1-PadE)") (class "Default")
      (node (ref "Q1") (pin "E") (pinfunction "E_E") (pintype "passive"))
      (node (ref "R58") (pin "2") (pinfunction "2_2") (pintype "passive"))
    )
    (net (code "24") (name "Net-(Q2-PadB)") (class "Default")
      (node (ref "Q2") (pin "B") (pinfunction "B_B") (pintype "passive"))
      (node (ref "R62") (pin "1") (pinfunction "1_1") (pintype "passive"))
      (node (ref "R63") (pin "2") (pinfunction "2_2") (pintype "passive"))
      (node (ref "R66") (pin "A") (pinfunction "A_A") (pintype "passive"))
      (node (ref "T6") (pin "E") (pinfunction "E_E") (pintype "passive"))
    )
    (net (code "25") (name "Net-(Q2-PadE)") (class "Default")
      (node (ref "Q2") (pin "E") (pinfunction "E_E") (pintype "passive"))
      (node (ref "R61") (pin "2") (pinfunction "2_2") (pintype "passive"))
    )
    (net (code "26") (name "Net-(Q3-PadB)") (class "Default")
      (node (ref "Q3") (pin "B") (pinfunction "B_B") (pintype "passive"))
      (node (ref "R70") (pin "1") (pinfunction "1_1") (pintype "passive"))
      (node (ref "R72") (pin "2") (pinfunction "2_2") (pintype "passive"))
      (node (ref "R73") (pin "A") (pinfunction "A_A") (pintype "passive"))
      (node (ref "T7") (pin "E") (pinfunction "E_E") (pintype "passive"))
    )
    (net (code "27") (name "Net-(Q3-PadE)") (class "Default")
      (node (ref "Q3") (pin "E") (pinfunction "E_E") (pintype "passive"))
      (node (ref "R68") (pin "2") (pinfunction "2_2") (pintype "passive"))
    )
    (net (code "28") (name "Net-(Q4-PadB)") (class "Default")
      (node (ref "Q4") (pin "B") (pinfunction "B_B") (pintype "passive"))
      (node (ref "R77") (pin "1") (pinfunction "1_1") (pintype "passive"))
      (node (ref "R78") (pin "2") (pinfunction "2_2") (pintype "passive"))
      (node (ref "R80") (pin "A") (pinfunction "A_A") (pintype "passive"))
      (node (ref "T8") (pin "E") (pinfunction "E_E") (pintype "passive"))
    )
    (net (code "29") (name "Net-(Q4-PadE)") (class "Default")
      (node (ref "Q4") (pin "E") (pinfunction "E_E") (pintype "passive"))
      (node (ref "R75") (pin "2") (pinfunction "2_2") (pintype "passive"))
    )
    (net (code "30") (name "Net-(R1-Pad1)") (class "Default")
      (node (ref "R1") (pin "1") (pinfunction "1_1") (pintype "passive"))
      (node (ref "R4") (pin "1E") (pinfunction "1E_1E") (pintype "passive"))
      (node (ref "R4") (pin "1S") (pinfunction "1S_1S") (pintype "passive"))
      (node (ref "SL1") (pin "2") (pinfunction "2_2") (pintype "passive"))
    )
    (net (code "31") (name "Net-(R1-Pad2)") (class "Default")
      (node (ref "R1") (pin "2") (pinfunction "2_2") (pintype "passive"))
      (node (ref "R29") (pin "2") (pinfunction "2_2") (pintype "passive"))
      (node (ref "R49") (pin "1") (pinfunction "1_1") (pintype "passive"))
      (node (ref "R57") (pin "2") (pinfunction "2_2") (pintype "passive"))
      (node (ref "R58") (pin "1") (pinfunction "1_1") (pintype "passive"))
      (node (ref "SL1") (pin "1") (pinfunction "1_1") (pintype "passive"))
    )
    (net (code "32") (name "Net-(R3-PadA)") (class "Default")
      (node (ref "R3") (pin "A") (pinfunction "A_A") (pintype "passive"))
      (node (ref "R6") (pin "1") (pinfunction "1_1") (pintype "passive"))
    )
    (net (code "33") (name "Net-(R3-PadE)") (class "Default")
      (node (ref "R3") (pin "E") (pinfunction "E_E") (pintype "passive"))
      (node (ref "R7") (pin "1") (pinfunction "1_1") (pintype "passive"))
    )
    (net (code "34") (name "Net-(R10-PadA)") (class "Default")
      (node (ref "R10") (pin "A") (pinfunction "A_A") (pintype "passive"))
      (node (ref "R13") (pin "1") (pinfunction "1_1") (pintype "passive"))
    )
    (net (code "35") (name "Net-(R10-PadE)") (class "Default")
      (node (ref "R10") (pin "E") (pinfunction "E_E") (pintype "passive"))
      (node (ref "R14") (pin "1") (pinfunction "1_1") (pintype "passive"))
    )
    (net (code "36") (name "Net-(R11-Pad1E)") (class "Default")
      (node (ref "R11") (pin "1E") (pinfunction "1E_1E") (pintype "passive"))
      (node (ref "R11") (pin "1S") (pinfunction "1S_1S") (pintype "passive"))
      (node (ref "R4") (pin "1A") (pinfunction "1A_1A") (pintype "passive"))
    )
    (net (code "37") (name "Net-(R15-Pad1)") (class "Default")
      (node (ref "R15") (pin "1") (pinfunction "1_1") (pintype "passive"))
      (node (ref "R37") (pin "1E") (pinfunction "1E_1E") (pintype "passive"))
      (node (ref "R37") (pin "1S") (pinfunction "1S_1S") (pintype "passive"))
      (node (ref "SL3") (pin "2") (pinfunction "2_2") (pintype "passive"))
    )
    (net (code "38") (name "Net-(R15-Pad2)") (class "Default")
      (node (ref "R15") (pin "2") (pinfunction "2_2") (pintype "passive"))
      (node (ref "R33") (pin "2") (pinfunction "2_2") (pintype "passive"))
      (node (ref "R51") (pin "1") (pinfunction "1_1") (pintype "passive"))
      (node (ref "R67") (pin "2") (pinfunction "2_2") (pintype "passive"))
      (node (ref "R68") (pin "1") (pinfunction "1_1") (pintype "passive"))
      (node (ref "SL3") (pin "1") (pinfunction "1_1") (pintype "passive"))
    )
    (net (code "39") (name "Net-(R17-PadA)") (class "Default")
      (node (ref "R17") (pin "A") (pinfunction "A_A") (pintype "passive"))
      (node (ref "R20") (pin "1") (pinfunction "1_1") (pintype "passive"))
    )
    (net (code "40") (name "Net-(R17-PadE)") (class "Default")
      (node (ref "R17") (pin "E") (pinfunction "E_E") (pintype "passive"))
      (node (ref "R21") (pin "1") (pinfunction "1_1") (pintype "passive"))
    )
    (net (code "41") (name "Net-(R18-Pad1A)") (class "Default")
      (node (ref "R18") (pin "1A") (pinfunction "1A_1A") (pintype "passive"))
      (node (ref "R25") (pin "1E") (pinfunction "1E_1E") (pintype "passive"))
      (node (ref "R25") (pin "1S") (pinfunction "1S_1S") (pintype "passive"))
    )
    (net (code "42") (name "Net-(R18-Pad1E)") (class "Default")
      (node (ref "R18") (pin "1E") (pinfunction "1E_1E") (pintype "passive"))
      (node (ref "R18") (pin "1S") (pinfunction "1S_1S") (pintype "passive"))
      (node (ref "R8") (pin "1") (pinfunction "1_1") (pintype "passive"))
      (node (ref "SL2") (pin "2") (pinfunction "2_2") (pintype "passive"))
    )
    (net (code "43") (name "Net-(R22-Pad1)") (class "Default")
      (node (ref "R22") (pin "1") (pinfunction "1_1") (pintype "passive"))
      (node (ref "R39") (pin "1E") (pinfunction "1E_1E") (pintype "passive"))
      (node (ref "R39") (pin "1S") (pinfunction "1S_1S") (pintype "passive"))
      (node (ref "SL4") (pin "2") (pinfunction "2_2") (pintype "passive"))
    )
    (net (code "44") (name "Net-(R22-Pad2)") (class "Default")
      (node (ref "R22") (pin "2") (pinfunction "2_2") (pintype "passive"))
      (node (ref "R35") (pin "2") (pinfunction "2_2") (pintype "passive"))
      (node (ref "R52") (pin "1") (pinfunction "1_1") (pintype "passive"))
      (node (ref "R74") (pin "2") (pinfunction "2_2") (pintype "passive"))
      (node (ref "R75") (pin "1") (pinfunction "1_1") (pintype "passive"))
      (node (ref "SL4") (pin "1") (pinfunction "1_1") (pintype "passive"))
    )
    (net (code "45") (name "Net-(R24-PadA)") (class "Default")
      (node (ref "R24") (pin "A") (pinfunction "A_A") (pintype "passive"))
      (node (ref "R27") (pin "1") (pinfunction "1_1") (pintype "passive"))
    )
    (net (code "46") (name "Net-(R24-PadE)") (class "Default")
      (node (ref "R24") (pin "E") (pinfunction "E_E") (pintype "passive"))
      (node (ref "R28") (pin "1") (pinfunction "1_1") (pintype "passive"))
    )
    (net (code "47") (name "Net-(R29-Pad1)") (class "Default")
      (node (ref "R29") (pin "1") (pinfunction "1_1") (pintype "passive"))
      (node (ref "R30") (pin "2") (pinfunction "2_2") (pintype "passive"))
    )
    (net (code "48") (name "Net-(R30-Pad1)") (class "Default")
      (node (ref "R30") (pin "1") (pinfunction "1_1") (pintype "passive"))
      (node (ref "R81") (pin "1") (pinfunction "1_1") (pintype "passive"))
      (node (ref "X1") (pin "1") (pinfunction "1_1") (pintype "passive"))
    )
    (net (code "49") (name "Net-(R31-Pad1)") (class "Default")
      (node (ref "R31") (pin "1") (pinfunction "1_1") (pintype "passive"))
      (node (ref "R32") (pin "2") (pinfunction "2_2") (pintype "passive"))
    )
    (net (code "50") (name "Net-(R31-Pad2)") (class "Default")
      (node (ref "R31") (pin "2") (pinfunction "2_2") (pintype "passive"))
      (node (ref "R50") (pin "1") (pinfunction "1_1") (pintype "passive"))
      (node (ref "R60") (pin "2") (pinfunction "2_2") (pintype "passive"))
      (node (ref "R61") (pin "1") (pinfunction "1_1") (pintype "passive"))
      (node (ref "R8") (pin "2") (pinfunction "2_2") (pintype "passive"))
      (node (ref "SL2") (pin "1") (pinfunction "1_1") (pintype "passive"))
    )
    (net (code "51") (name "Net-(R32-Pad1)") (class "Default")
      (node (ref "R32") (pin "1") (pinfunction "1_1") (pintype "passive"))
      (node (ref "R82") (pin "1") (pinfunction "1_1") (pintype "passive"))
      (node (ref "X2") (pin "1") (pinfunction "1_1") (pintype "passive"))
    )
    (net (code "52") (name "Net-(R33-Pad1)") (class "Default")
      (node (ref "R33") (pin "1") (pinfunction "1_1") (pintype "passive"))
      (node (ref "R34") (pin "2") (pinfunction "2_2") (pintype "passive"))
    )
    (net (code "53") (name "Net-(R34-Pad1)") (class "Default")
      (node (ref "R34") (pin "1") (pinfunction "1_1") (pintype "passive"))
      (node (ref "R83") (pin "1") (pinfunction "1_1") (pintype "passive"))
      (node (ref "X3") (pin "1") (pinfunction "1_1") (pintype "passive"))
    )
    (net (code "54") (name "Net-(R35-Pad1)") (class "Default")
      (node (ref "R35") (pin "1") (pinfunction "1_1") (pintype "passive"))
      (node (ref "R36") (pin "2") (pinfunction "2_2") (pintype "passive"))
    )
    (net (code "55") (name "Net-(R36-Pad1)") (class "Default")
      (node (ref "R36") (pin "1") (pinfunction "1_1") (pintype "passive"))
      (node (ref "R84") (pin "1") (pinfunction "1_1") (pintype "passive"))
      (node (ref "X4") (pin "1") (pinfunction "1_1") (pintype "passive"))
    )
    (net (code "56") (name "Net-(R37-Pad1A)") (class "Default")
      (node (ref "R37") (pin "1A") (pinfunction "1A_1A") (pintype "passive"))
      (node (ref "R38") (pin "1E") (pinfunction "1E_1E") (pintype "passive"))
      (node (ref "R38") (pin "1S") (pinfunction "1S_1S") (pintype "passive"))
    )
    (net (code "57") (name "Net-(R39-Pad1A)") (class "Default")
      (node (ref "R39") (pin "1A") (pinfunction "1A_1A") (pintype "passive"))
      (node (ref "R40") (pin "1E") (pinfunction "1E_1E") (pintype "passive"))
      (node (ref "R40") (pin "1S") (pinfunction "1S_1S") (pintype "passive"))
    )
    (net (code "58") (name "Net-(R41-Pad1)") (class "Default")
      (node (ref "R41") (pin "1") (pinfunction "1_1") (pintype "passive"))
      (node (ref "R42") (pin "1") (pinfunction "1_1") (pintype "passive"))
      (node (ref "SL5") (pin "1") (pinfunction "1_1") (pintype "passive"))
      (node (ref "SL5") (pin "2") (pinfunction "2_2") (pintype "passive"))
    )
    (net (code "59") (name "Net-(R43-Pad1)") (class "Default")
      (node (ref "R43") (pin "1") (pinfunction "1_1") (pintype "passive"))
      (node (ref "R44") (pin "1") (pinfunction "1_1") (pintype "passive"))
      (node (ref "SL6") (pin "1") (pinfunction "1_1") (pintype "passive"))
      (node (ref "SL6") (pin "2") (pinfunction "2_2") (pintype "passive"))
    )
    (net (code "60") (name "Net-(R45-Pad1)") (class "Default")
      (node (ref "R45") (pin "1") (pinfunction "1_1") (pintype "passive"))
      (node (ref "R46") (pin "1") (pinfunction "1_1") (pintype "passive"))
      (node (ref "SL7") (pin "1") (pinfunction "1_1") (pintype "passive"))
      (node (ref "SL7") (pin "2") (pinfunction "2_2") (pintype "passive"))
    )
    (net (code "61") (name "Net-(R47-Pad1)") (class "Default")
      (node (ref "R47") (pin "1") (pinfunction "1_1") (pintype "passive"))
      (node (ref "R48") (pin "1") (pinfunction "1_1") (pintype "passive"))
      (node (ref "SL8") (pin "1") (pinfunction "1_1") (pintype "passive"))
      (node (ref "SL8") (pin "2") (pinfunction "2_2") (pintype "passive"))
    )
    (net (code "62") (name "Net-(R53-Pad1)") (class "Default")
      (node (ref "R53") (pin "1") (pinfunction "1_1") (pintype "passive"))
      (node (ref "R55") (pin "1") (pinfunction "1_1") (pintype "passive"))
      (node (ref "R59") (pin "E") (pinfunction "E_E") (pintype "passive"))
      (node (ref "T1") (pin "B") (pinfunction "B_B") (pintype "passive"))
      (node (ref "T5") (pin "C") (pinfunction "C_C") (pintype "passive"))
    )
    (net (code "63") (name "Net-(R57-Pad1)") (class "Default")
      (node (ref "R57") (pin "1") (pinfunction "1_1") (pintype "passive"))
      (node (ref "T1") (pin "E") (pinfunction "E_E") (pintype "passive"))
    )
    (net (code "64") (name "Net-(R59-PadS)") (class "Default")
      (node (ref "R59") (pin "S") (pinfunction "S_S") (pintype "passive"))
      (node (ref "T5") (pin "B") (pinfunction "B_B") (pintype "passive"))
    )
    (net (code "65") (name "Net-(R60-Pad1)") (class "Default")
      (node (ref "R60") (pin "1") (pinfunction "1_1") (pintype "passive"))
      (node (ref "T2") (pin "E") (pinfunction "E_E") (pintype "passive"))
    )
    (net (code "66") (name "Net-(R64-Pad1)") (class "Default")
      (node (ref "R64") (pin "1") (pinfunction "1_1") (pintype "passive"))
      (node (ref "R65") (pin "1") (pinfunction "1_1") (pintype "passive"))
      (node (ref "R66") (pin "E") (pinfunction "E_E") (pintype "passive"))
      (node (ref "T2") (pin "B") (pinfunction "B_B") (pintype "passive"))
      (node (ref "T6") (pin "C") (pinfunction "C_C") (pintype "passive"))
    )
    (net (code "67") (name "Net-(R66-PadS)") (class "Default")
      (node (ref "R66") (pin "S") (pinfunction "S_S") (pintype "passive"))
      (node (ref "T6") (pin "B") (pinfunction "B_B") (pintype "passive"))
    )
    (net (code "68") (name "Net-(R67-Pad1)") (class "Default")
      (node (ref "R67") (pin "1") (pinfunction "1_1") (pintype "passive"))
      (node (ref "T3") (pin "E") (pinfunction "E_E") (pintype "passive"))
    )
    (net (code "69") (name "Net-(R69-Pad1)") (class "Default")
      (node (ref "R69") (pin "1") (pinfunction "1_1") (pintype "passive"))
      (node (ref "R71") (pin "1") (pinfunction "1_1") (pintype "passive"))
      (node (ref "R73") (pin "E") (pinfunction "E_E") (pintype "passive"))
      (node (ref "T3") (pin "B") (pinfunction "B_B") (pintype "passive"))
      (node (ref "T7") (pin "C") (pinfunction "C_C") (pintype "passive"))
    )
    (net (code "70") (name "Net-(R73-PadS)") (class "Default")
      (node (ref "R73") (pin "S") (pinfunction "S_S") (pintype "passive"))
      (node (ref "T7") (pin "B") (pinfunction "B_B") (pintype "passive"))
    )
    (net (code "71") (name "Net-(R74-Pad1)") (class "Default")
      (node (ref "R74") (pin "1") (pinfunction "1_1") (pintype "passive"))
      (node (ref "T4") (pin "E") (pinfunction "E_E") (pintype "passive"))
    )
    (net (code "72") (name "Net-(R76-Pad1)") (class "Default")
      (node (ref "R76") (pin "1") (pinfunction "1_1") (pintype "passive"))
      (node (ref "R79") (pin "1") (pinfunction "1_1") (pintype "passive"))
      (node (ref "R80") (pin "E") (pinfunction "E_E") (pintype "passive"))
      (node (ref "T4") (pin "B") (pinfunction "B_B") (pintype "passive"))
      (node (ref "T8") (pin "C") (pinfunction "C_C") (pintype "passive"))
    )
    (net (code "73") (name "Net-(R80-PadS)") (class "Default")
      (node (ref "R80") (pin "S") (pinfunction "S_S") (pintype "passive"))
      (node (ref "T8") (pin "B") (pinfunction "B_B") (pintype "passive"))
    )
    (net (code "74") (name "VDD") (class "Default")
      (node (ref "C1") (pin "1") (pinfunction "1_1") (pintype "passive"))
      (node (ref "C10") (pin "+") (pinfunction "+_+") (pintype "passive"))
      (node (ref "C13") (pin "+") (pinfunction "+_+") (pintype "passive"))
      (node (ref "C14") (pin "+") (pinfunction "+_+") (pintype "passive"))
      (node (ref "C17") (pin "1") (pinfunction "1_1") (pintype "passive"))
      (node (ref "C18") (pin "1") (pinfunction "1_1") (pintype "passive"))
      (node (ref "C19") (pin "1") (pinfunction "1_1") (pintype "passive"))
      (node (ref "C20") (pin "1") (pinfunction "1_1") (pintype "passive"))
      (node (ref "C3") (pin "1") (pinfunction "1_1") (pintype "passive"))
      (node (ref "C5") (pin "1") (pinfunction "1_1") (pintype "passive"))
      (node (ref "C8") (pin "1") (pinfunction "1_1") (pintype "passive"))
      (node (ref "C9") (pin "+") (pinfunction "+_+") (pintype "passive"))
      (node (ref "IC1") (pin "7") (pinfunction "V+_7") (pintype "power_in"))
      (node (ref "IC2") (pin "7") (pinfunction "V+_7") (pintype "power_in"))
      (node (ref "IC3") (pin "7") (pinfunction "V+_7") (pintype "power_in"))
      (node (ref "IC4") (pin "7") (pinfunction "V+_7") (pintype "power_in"))
      (node (ref "PAD1") (pin "1") (pinfunction "P_1") (pintype "passive"))
      (node (ref "R55") (pin "2") (pinfunction "2_2") (pintype "passive"))
      (node (ref "R64") (pin "2") (pinfunction "2_2") (pintype "passive"))
      (node (ref "R69") (pin "2") (pinfunction "2_2") (pintype "passive"))
      (node (ref "R76") (pin "2") (pinfunction "2_2") (pintype "passive"))
      (node (ref "T1") (pin "C") (pinfunction "C_C") (pintype "passive"))
      (node (ref "T2") (pin "C") (pinfunction "C_C") (pintype "passive"))
      (node (ref "T3") (pin "C") (pinfunction "C_C") (pintype "passive"))
      (node (ref "T4") (pin "C") (pinfunction "C_C") (pintype "passive"))
    )
    (net (code "75") (name "VSS") (class "Default")
      (node (ref "C11") (pin "-") (pinfunction "-_-") (pintype "passive"))
      (node (ref "C12") (pin "-") (pinfunction "-_-") (pintype "passive"))
      (node (ref "C15") (pin "-") (pinfunction "-_-") (pintype "passive"))
      (node (ref "C16") (pin "-") (pinfunction "-_-") (pintype "passive"))
      (node (ref "C2") (pin "2") (pinfunction "2_2") (pintype "passive"))
      (node (ref "C21") (pin "2") (pinfunction "2_2") (pintype "passive"))
      (node (ref "C22") (pin "2") (pinfunction "2_2") (pintype "passive"))
      (node (ref "C23") (pin "2") (pinfunction "2_2") (pintype "passive"))
      (node (ref "C24") (pin "2") (pinfunction "2_2") (pintype "passive"))
      (node (ref "C4") (pin "2") (pinfunction "2_2") (pintype "passive"))
      (node (ref "C6") (pin "2") (pinfunction "2_2") (pintype "passive"))
      (node (ref "C7") (pin "2") (pinfunction "2_2") (pintype "passive"))
      (node (ref "IC1") (pin "4") (pinfunction "V-_4") (pintype "power_in"))
      (node (ref "IC2") (pin "4") (pinfunction "V-_4") (pintype "power_in"))
      (node (ref "IC3") (pin "4") (pinfunction "V-_4") (pintype "power_in"))
      (node (ref "IC4") (pin "4") (pinfunction "V-_4") (pintype "power_in"))
      (node (ref "PAD3") (pin "1") (pinfunction "P_1") (pintype "passive"))
      (node (ref "Q1") (pin "C") (pinfunction "C_C") (pintype "passive"))
      (node (ref "Q2") (pin "C") (pinfunction "C_C") (pintype "passive"))
      (node (ref "Q3") (pin "C") (pinfunction "C_C") (pintype "passive"))
      (node (ref "Q4") (pin "C") (pinfunction "C_C") (pintype "passive"))
      (node (ref "R10") (pin "S") (pinfunction "S_S") (pintype "passive"))
      (node (ref "R17") (pin "S") (pinfunction "S_S") (pintype "passive"))
      (node (ref "R24") (pin "S") (pinfunction "S_S") (pintype "passive"))
      (node (ref "R3") (pin "S") (pinfunction "S_S") (pintype "passive"))
      (node (ref "R56") (pin "2") (pinfunction "2_2") (pintype "passive"))
      (node (ref "R62") (pin "2") (pinfunction "2_2") (pintype "passive"))
      (node (ref "R70") (pin "2") (pinfunction "2_2") (pintype "passive"))
      (node (ref "R77") (pin "2") (pinfunction "2_2") (pintype "passive"))
    )
    (net (code "76") (name "unconnected-(IC1-OPT-Pad8)") (class "Default")
      (node (ref "IC1") (pin "8") (pinfunction "OPT_8") (pintype "passive"))
    )
    (net (code "77") (name "unconnected-(IC2-OPT-Pad8)") (class "Default")
      (node (ref "IC2") (pin "8") (pinfunction "OPT_8") (pintype "passive"))
    )
    (net (code "78") (name "unconnected-(IC3-OPT-Pad8)") (class "Default")
      (node (ref "IC3") (pin "8") (pinfunction "OPT_8") (pintype "passive"))
    )
    (net (code "79") (name "unconnected-(IC4-OPT-Pad8)") (class "Default")
      (node (ref "IC4") (pin "8") (pinfunction "OPT_8") (pintype "passive"))
    )
    (net (code "80") (name "unconnected-(SV2-Pad9)") (class "Default")
      (node (ref "SV2") (pin "9") (pinfunction "9_9") (pintype "passive"))
    )
  )
)
